# untitled.net
KiCad netlist of a schematic drawn in EAGLE
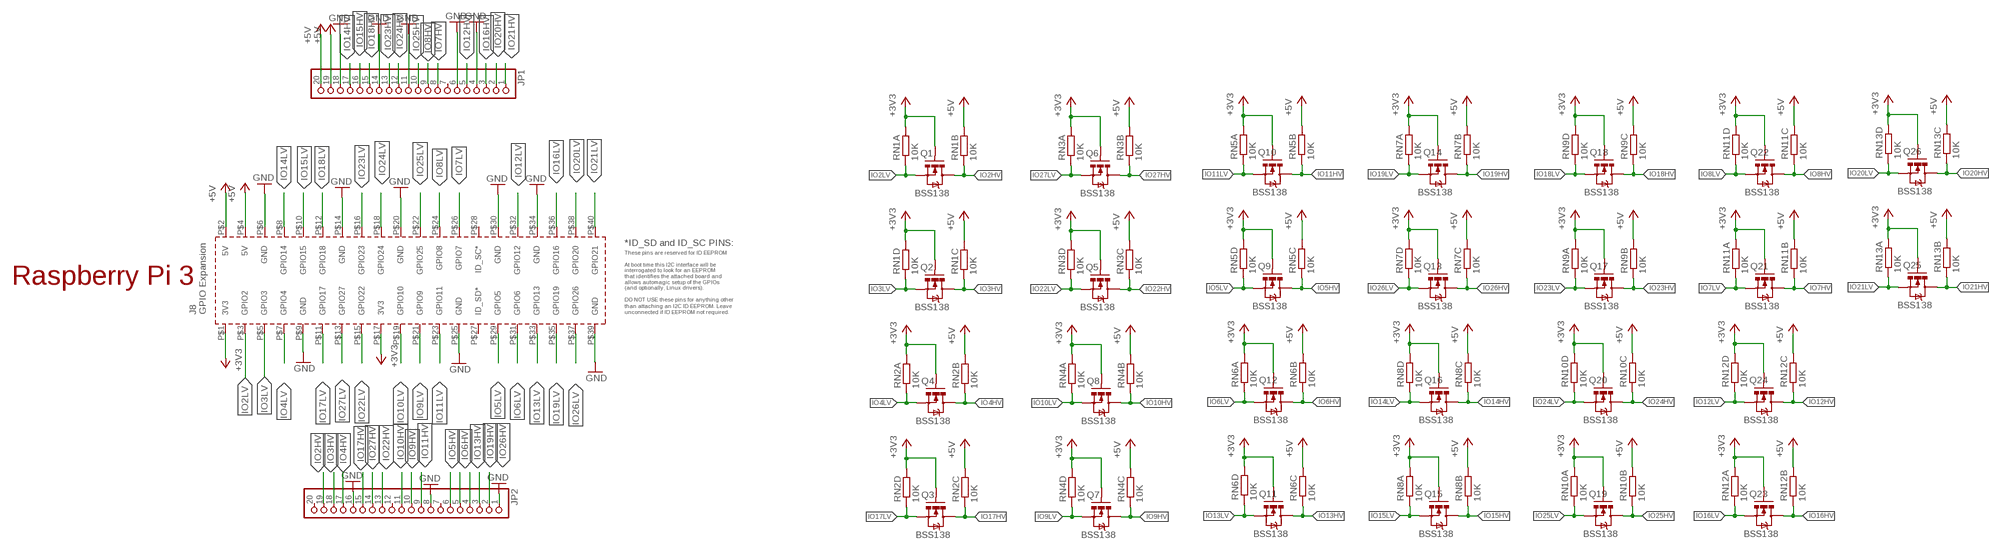
[diagram p0: schematic, sheet 1]

(export (version "E")
  (design (tool "Eeschema 10.0.6"))
  (components
    (comp (ref "JP1")
      (value "PINHD-1X20-BIG")
      (footprint "eagle-import:1X20-BIG")
      (libsource (lib "eagle-import") (part "PINHD-1X20-BIG"))
    )
    (comp (ref "JP2")
      (value "PINHD-1X20-BIG")
      (footprint "eagle-import:1X20-BIG")
      (libsource (lib "eagle-import") (part "PINHD-1X20-BIG"))
    )
    (comp (ref "Q1")
      (value "BSS138")
      (footprint "eagle-import:SOT23-3")
      (libsource (lib "eagle-import") (part "MOSFET-NCHANNELSMD"))
    )
    (comp (ref "Q2")
      (value "BSS138")
      (footprint "eagle-import:SOT23-3")
      (libsource (lib "eagle-import") (part "MOSFET-NCHANNELSMD"))
    )
    (comp (ref "Q3")
      (value "BSS138")
      (footprint "eagle-import:SOT23-3")
      (libsource (lib "eagle-import") (part "MOSFET-NCHANNELSMD"))
    )
    (comp (ref "Q4")
      (value "BSS138")
      (footprint "eagle-import:SOT23-3")
      (libsource (lib "eagle-import") (part "MOSFET-NCHANNELSMD"))
    )
    (comp (ref "Q5")
      (value "BSS138")
      (footprint "eagle-import:SOT23-3")
      (libsource (lib "eagle-import") (part "MOSFET-NCHANNELSMD"))
    )
    (comp (ref "Q6")
      (value "BSS138")
      (footprint "eagle-import:SOT23-3")
      (libsource (lib "eagle-import") (part "MOSFET-NCHANNELSMD"))
    )
    (comp (ref "Q7")
      (value "BSS138")
      (footprint "eagle-import:SOT23-3")
      (libsource (lib "eagle-import") (part "MOSFET-NCHANNELSMD"))
    )
    (comp (ref "Q8")
      (value "BSS138")
      (footprint "eagle-import:SOT23-3")
      (libsource (lib "eagle-import") (part "MOSFET-NCHANNELSMD"))
    )
    (comp (ref "Q9")
      (value "BSS138")
      (footprint "eagle-import:SOT23-3")
      (libsource (lib "eagle-import") (part "MOSFET-NCHANNELSMD"))
    )
    (comp (ref "Q10")
      (value "BSS138")
      (footprint "eagle-import:SOT23-3")
      (libsource (lib "eagle-import") (part "MOSFET-NCHANNELSMD"))
    )
    (comp (ref "Q11")
      (value "BSS138")
      (footprint "eagle-import:SOT23-3")
      (libsource (lib "eagle-import") (part "MOSFET-NCHANNELSMD"))
    )
    (comp (ref "Q12")
      (value "BSS138")
      (footprint "eagle-import:SOT23-3")
      (libsource (lib "eagle-import") (part "MOSFET-NCHANNELSMD"))
    )
    (comp (ref "Q13")
      (value "BSS138")
      (footprint "eagle-import:SOT23-3")
      (libsource (lib "eagle-import") (part "MOSFET-NCHANNELSMD"))
    )
    (comp (ref "Q14")
      (value "BSS138")
      (footprint "eagle-import:SOT23-3")
      (libsource (lib "eagle-import") (part "MOSFET-NCHANNELSMD"))
    )
    (comp (ref "Q15")
      (value "BSS138")
      (footprint "eagle-import:SOT23-3")
      (libsource (lib "eagle-import") (part "MOSFET-NCHANNELSMD"))
    )
    (comp (ref "Q16")
      (value "BSS138")
      (footprint "eagle-import:SOT23-3")
      (libsource (lib "eagle-import") (part "MOSFET-NCHANNELSMD"))
    )
    (comp (ref "Q17")
      (value "BSS138")
      (footprint "eagle-import:SOT23-3")
      (libsource (lib "eagle-import") (part "MOSFET-NCHANNELSMD"))
    )
    (comp (ref "Q18")
      (value "BSS138")
      (footprint "eagle-import:SOT23-3")
      (libsource (lib "eagle-import") (part "MOSFET-NCHANNELSMD"))
    )
    (comp (ref "Q19")
      (value "BSS138")
      (footprint "eagle-import:SOT23-3")
      (libsource (lib "eagle-import") (part "MOSFET-NCHANNELSMD"))
    )
    (comp (ref "Q20")
      (value "BSS138")
      (footprint "eagle-import:SOT23-3")
      (libsource (lib "eagle-import") (part "MOSFET-NCHANNELSMD"))
    )
    (comp (ref "Q21")
      (value "BSS138")
      (footprint "eagle-import:SOT23-3")
      (libsource (lib "eagle-import") (part "MOSFET-NCHANNELSMD"))
    )
    (comp (ref "Q22")
      (value "BSS138")
      (footprint "eagle-import:SOT23-3")
      (libsource (lib "eagle-import") (part "MOSFET-NCHANNELSMD"))
    )
    (comp (ref "Q23")
      (value "BSS138")
      (footprint "eagle-import:SOT23-3")
      (libsource (lib "eagle-import") (part "MOSFET-NCHANNELSMD"))
    )
    (comp (ref "Q24")
      (value "BSS138")
      (footprint "eagle-import:SOT23-3")
      (libsource (lib "eagle-import") (part "MOSFET-NCHANNELSMD"))
    )
    (comp (ref "Q25")
      (value "BSS138")
      (footprint "eagle-import:SOT23-3")
      (libsource (lib "eagle-import") (part "MOSFET-NCHANNELSMD"))
    )
    (comp (ref "Q26")
      (value "BSS138")
      (footprint "eagle-import:SOT23-3")
      (libsource (lib "eagle-import") (part "MOSFET-NCHANNELSMD"))
    )
    (comp (ref "RN1")
      (value "10K")
      (footprint "eagle-import:RN8P-4R-CRA06S")
      (libsource (lib "eagle-import") (part "RESISTOR_ARRAY_4"))
    )
    (comp (ref "RN2")
      (value "10K")
      (footprint "eagle-import:RN8P-4R-CRA06S")
      (libsource (lib "eagle-import") (part "RESISTOR_ARRAY_4"))
    )
    (comp (ref "RN3")
      (value "10K")
      (footprint "eagle-import:RN8P-4R-CRA06S")
      (libsource (lib "eagle-import") (part "RESISTOR_ARRAY_4"))
    )
    (comp (ref "RN4")
      (value "10K")
      (footprint "eagle-import:RN8P-4R-CRA06S")
      (libsource (lib "eagle-import") (part "RESISTOR_ARRAY_4"))
    )
    (comp (ref "RN5")
      (value "10K")
      (footprint "eagle-import:RN8P-4R-CRA06S")
      (libsource (lib "eagle-import") (part "RESISTOR_ARRAY_4"))
    )
    (comp (ref "RN6")
      (value "10K")
      (footprint "eagle-import:RN8P-4R-CRA06S")
      (libsource (lib "eagle-import") (part "RESISTOR_ARRAY_4"))
    )
    (comp (ref "RN7")
      (value "10K")
      (footprint "eagle-import:RN8P-4R-CRA06S")
      (libsource (lib "eagle-import") (part "RESISTOR_ARRAY_4"))
    )
    (comp (ref "RN8")
      (value "10K")
      (footprint "eagle-import:RN8P-4R-CRA06S")
      (libsource (lib "eagle-import") (part "RESISTOR_ARRAY_4"))
    )
    (comp (ref "RN9")
      (value "10K")
      (footprint "eagle-import:RN8P-4R-CRA06S")
      (libsource (lib "eagle-import") (part "RESISTOR_ARRAY_4"))
    )
    (comp (ref "RN10")
      (value "10K")
      (footprint "eagle-import:RN8P-4R-CRA06S")
      (libsource (lib "eagle-import") (part "RESISTOR_ARRAY_4"))
    )
    (comp (ref "RN11")
      (value "10K")
      (footprint "eagle-import:RN8P-4R-CRA06S")
      (libsource (lib "eagle-import") (part "RESISTOR_ARRAY_4"))
    )
    (comp (ref "RN12")
      (value "10K")
      (footprint "eagle-import:RN8P-4R-CRA06S")
      (libsource (lib "eagle-import") (part "RESISTOR_ARRAY_4"))
    )
    (comp (ref "RN13")
      (value "10K")
      (footprint "eagle-import:RN8P-4R-CRA06S")
      (libsource (lib "eagle-import") (part "RESISTOR_ARRAY_4"))
    )
    (comp (ref "U$2")
      (value "RPI3HEADERS")
      (footprint "eagle-import:RPI3HEADERS")
      (libsource (lib "eagle-import") (part "RPI3HEADERS"))
    )
  )
  (nets
    (net (code "1") (name "+3V3") (class "Default")
      (node (ref "Q1") (pin "1") (pinfunction "G_1") (pintype "passive"))
      (node (ref "Q10") (pin "1") (pinfunction "G_1") (pintype "passive"))
      (node (ref "Q11") (pin "1") (pinfunction "G_1") (pintype "passive"))
      (node (ref "Q12") (pin "1") (pinfunction "G_1") (pintype "passive"))
      (node (ref "Q13") (pin "1") (pinfunction "G_1") (pintype "passive"))
      (node (ref "Q14") (pin "1") (pinfunction "G_1") (pintype "passive"))
      (node (ref "Q15") (pin "1") (pinfunction "G_1") (pintype "passive"))
      (node (ref "Q16") (pin "1") (pinfunction "G_1") (pintype "passive"))
      (node (ref "Q17") (pin "1") (pinfunction "G_1") (pintype "passive"))
      (node (ref "Q18") (pin "1") (pinfunction "G_1") (pintype "passive"))
      (node (ref "Q19") (pin "1") (pinfunction "G_1") (pintype "passive"))
      (node (ref "Q2") (pin "1") (pinfunction "G_1") (pintype "passive"))
      (node (ref "Q20") (pin "1") (pinfunction "G_1") (pintype "passive"))
      (node (ref "Q21") (pin "1") (pinfunction "G_1") (pintype "passive"))
      (node (ref "Q22") (pin "1") (pinfunction "G_1") (pintype "passive"))
      (node (ref "Q23") (pin "1") (pinfunction "G_1") (pintype "passive"))
      (node (ref "Q24") (pin "1") (pinfunction "G_1") (pintype "passive"))
      (node (ref "Q25") (pin "1") (pinfunction "G_1") (pintype "passive"))
      (node (ref "Q26") (pin "1") (pinfunction "G_1") (pintype "passive"))
      (node (ref "Q3") (pin "1") (pinfunction "G_1") (pintype "passive"))
      (node (ref "Q4") (pin "1") (pinfunction "G_1") (pintype "passive"))
      (node (ref "Q5") (pin "1") (pinfunction "G_1") (pintype "passive"))
      (node (ref "Q6") (pin "1") (pinfunction "G_1") (pintype "passive"))
      (node (ref "Q7") (pin "1") (pinfunction "G_1") (pintype "passive"))
      (node (ref "Q8") (pin "1") (pinfunction "G_1") (pintype "passive"))
      (node (ref "Q9") (pin "1") (pinfunction "G_1") (pintype "passive"))
      (node (ref "RN1") (pin "5") (pinfunction "2_5") (pintype "passive"))
      (node (ref "RN1") (pin "8") (pinfunction "2_8") (pintype "passive"))
      (node (ref "RN10") (pin "5") (pinfunction "2_5") (pintype "passive"))
      (node (ref "RN10") (pin "8") (pinfunction "2_8") (pintype "passive"))
      (node (ref "RN11") (pin "5") (pinfunction "2_5") (pintype "passive"))
      (node (ref "RN11") (pin "8") (pinfunction "2_8") (pintype "passive"))
      (node (ref "RN12") (pin "5") (pinfunction "2_5") (pintype "passive"))
      (node (ref "RN12") (pin "8") (pinfunction "2_8") (pintype "passive"))
      (node (ref "RN13") (pin "5") (pinfunction "2_5") (pintype "passive"))
      (node (ref "RN13") (pin "8") (pinfunction "2_8") (pintype "passive"))
      (node (ref "RN2") (pin "5") (pinfunction "2_5") (pintype "passive"))
      (node (ref "RN2") (pin "8") (pinfunction "2_8") (pintype "passive"))
      (node (ref "RN3") (pin "5") (pinfunction "2_5") (pintype "passive"))
      (node (ref "RN3") (pin "8") (pinfunction "2_8") (pintype "passive"))
      (node (ref "RN4") (pin "5") (pinfunction "2_5") (pintype "passive"))
      (node (ref "RN4") (pin "8") (pinfunction "2_8") (pintype "passive"))
      (node (ref "RN5") (pin "5") (pinfunction "2_5") (pintype "passive"))
      (node (ref "RN5") (pin "8") (pinfunction "2_8") (pintype "passive"))
      (node (ref "RN6") (pin "5") (pinfunction "2_5") (pintype "passive"))
      (node (ref "RN6") (pin "8") (pinfunction "2_8") (pintype "passive"))
      (node (ref "RN7") (pin "5") (pinfunction "2_5") (pintype "passive"))
      (node (ref "RN7") (pin "8") (pinfunction "2_8") (pintype "passive"))
      (node (ref "RN8") (pin "5") (pinfunction "2_5") (pintype "passive"))
      (node (ref "RN8") (pin "8") (pinfunction "2_8") (pintype "passive"))
      (node (ref "RN9") (pin "5") (pinfunction "2_5") (pintype "passive"))
      (node (ref "RN9") (pin "8") (pinfunction "2_8") (pintype "passive"))
      (node (ref "U$2") (pin "P$1") (pinfunction "3V3_P$1") (pintype "bidirectional"))
      (node (ref "U$2") (pin "P$17") (pinfunction "3V3_P$17") (pintype "bidirectional"))
    )
    (net (code "2") (name "+5V") (class "Default")
      (node (ref "JP1") (pin "19") (pinfunction "19_19") (pintype "passive"))
      (node (ref "JP1") (pin "20") (pinfunction "20_20") (pintype "passive"))
      (node (ref "RN1") (pin "6") (pinfunction "2_6") (pintype "passive"))
      (node (ref "RN1") (pin "7") (pinfunction "2_7") (pintype "passive"))
      (node (ref "RN10") (pin "6") (pinfunction "2_6") (pintype "passive"))
      (node (ref "RN10") (pin "7") (pinfunction "2_7") (pintype "passive"))
      (node (ref "RN11") (pin "6") (pinfunction "2_6") (pintype "passive"))
      (node (ref "RN11") (pin "7") (pinfunction "2_7") (pintype "passive"))
      (node (ref "RN12") (pin "6") (pinfunction "2_6") (pintype "passive"))
      (node (ref "RN12") (pin "7") (pinfunction "2_7") (pintype "passive"))
      (node (ref "RN13") (pin "6") (pinfunction "2_6") (pintype "passive"))
      (node (ref "RN13") (pin "7") (pinfunction "2_7") (pintype "passive"))
      (node (ref "RN2") (pin "6") (pinfunction "2_6") (pintype "passive"))
      (node (ref "RN2") (pin "7") (pinfunction "2_7") (pintype "passive"))
      (node (ref "RN3") (pin "6") (pinfunction "2_6") (pintype "passive"))
      (node (ref "RN3") (pin "7") (pinfunction "2_7") (pintype "passive"))
      (node (ref "RN4") (pin "6") (pinfunction "2_6") (pintype "passive"))
      (node (ref "RN4") (pin "7") (pinfunction "2_7") (pintype "passive"))
      (node (ref "RN5") (pin "6") (pinfunction "2_6") (pintype "passive"))
      (node (ref "RN5") (pin "7") (pinfunction "2_7") (pintype "passive"))
      (node (ref "RN6") (pin "6") (pinfunction "2_6") (pintype "passive"))
      (node (ref "RN6") (pin "7") (pinfunction "2_7") (pintype "passive"))
      (node (ref "RN7") (pin "6") (pinfunction "2_6") (pintype "passive"))
      (node (ref "RN7") (pin "7") (pinfunction "2_7") (pintype "passive"))
      (node (ref "RN8") (pin "6") (pinfunction "2_6") (pintype "passive"))
      (node (ref "RN8") (pin "7") (pinfunction "2_7") (pintype "passive"))
      (node (ref "RN9") (pin "6") (pinfunction "2_6") (pintype "passive"))
      (node (ref "RN9") (pin "7") (pinfunction "2_7") (pintype "passive"))
      (node (ref "U$2") (pin "P$2") (pinfunction "5V_P$2") (pintype "bidirectional"))
      (node (ref "U$2") (pin "P$4") (pinfunction "5V_P$4") (pintype "bidirectional"))
    )
    (net (code "3") (name "GND") (class "Default")
      (node (ref "JP1") (pin "11") (pinfunction "11_11") (pintype "passive"))
      (node (ref "JP1") (pin "14") (pinfunction "14_14") (pintype "passive"))
      (node (ref "JP1") (pin "18") (pinfunction "18_18") (pintype "passive"))
      (node (ref "JP1") (pin "4") (pinfunction "4_4") (pintype "passive"))
      (node (ref "JP1") (pin "6") (pinfunction "6_6") (pintype "passive"))
      (node (ref "JP2") (pin "1") (pinfunction "1_1") (pintype "passive"))
      (node (ref "JP2") (pin "16") (pinfunction "16_16") (pintype "passive"))
      (node (ref "JP2") (pin "8") (pinfunction "8_8") (pintype "passive"))
      (node (ref "U$2") (pin "P$14") (pinfunction "GND_P$14") (pintype "bidirectional"))
      (node (ref "U$2") (pin "P$20") (pinfunction "GND_P$20") (pintype "bidirectional"))
      (node (ref "U$2") (pin "P$25") (pinfunction "GND_P$25") (pintype "bidirectional"))
      (node (ref "U$2") (pin "P$30") (pinfunction "GND_P$30") (pintype "bidirectional"))
      (node (ref "U$2") (pin "P$34") (pinfunction "GND_P$34") (pintype "bidirectional"))
      (node (ref "U$2") (pin "P$39") (pinfunction "GND_P$39") (pintype "bidirectional"))
      (node (ref "U$2") (pin "P$6") (pinfunction "GND_P$6") (pintype "bidirectional"))
      (node (ref "U$2") (pin "P$9") (pinfunction "GND_P$9") (pintype "bidirectional"))
    )
    (net (code "4") (name "IO2HV") (class "Default")
      (node (ref "JP2") (pin "19") (pinfunction "19_19") (pintype "passive"))
      (node (ref "Q1") (pin "3") (pinfunction "D_3") (pintype "passive"))
      (node (ref "RN1") (pin "2") (pinfunction "1_2") (pintype "passive"))
    )
    (net (code "5") (name "IO2LV") (class "Default")
      (node (ref "Q1") (pin "2") (pinfunction "S_2") (pintype "passive"))
      (node (ref "RN1") (pin "1") (pinfunction "1_1") (pintype "passive"))
      (node (ref "U$2") (pin "P$3") (pinfunction "GPIO2_P$3") (pintype "bidirectional"))
    )
    (net (code "6") (name "IO3HV") (class "Default")
      (node (ref "JP2") (pin "18") (pinfunction "18_18") (pintype "passive"))
      (node (ref "Q2") (pin "3") (pinfunction "D_3") (pintype "passive"))
      (node (ref "RN1") (pin "3") (pinfunction "1_3") (pintype "passive"))
    )
    (net (code "7") (name "IO3LV") (class "Default")
      (node (ref "Q2") (pin "2") (pinfunction "S_2") (pintype "passive"))
      (node (ref "RN1") (pin "4") (pinfunction "1_4") (pintype "passive"))
      (node (ref "U$2") (pin "P$5") (pinfunction "GPIO3_P$5") (pintype "bidirectional"))
    )
    (net (code "8") (name "IO4HV") (class "Default")
      (node (ref "JP2") (pin "17") (pinfunction "17_17") (pintype "passive"))
      (node (ref "Q4") (pin "3") (pinfunction "D_3") (pintype "passive"))
      (node (ref "RN2") (pin "2") (pinfunction "1_2") (pintype "passive"))
    )
    (net (code "9") (name "IO4LV") (class "Default")
      (node (ref "Q4") (pin "2") (pinfunction "S_2") (pintype "passive"))
      (node (ref "RN2") (pin "1") (pinfunction "1_1") (pintype "passive"))
      (node (ref "U$2") (pin "P$7") (pinfunction "GPIO4_P$7") (pintype "bidirectional"))
    )
    (net (code "10") (name "IO5HV") (class "Default")
      (node (ref "JP2") (pin "6") (pinfunction "6_6") (pintype "passive"))
      (node (ref "Q9") (pin "3") (pinfunction "D_3") (pintype "passive"))
      (node (ref "RN5") (pin "3") (pinfunction "1_3") (pintype "passive"))
    )
    (net (code "11") (name "IO5LV") (class "Default")
      (node (ref "Q9") (pin "2") (pinfunction "S_2") (pintype "passive"))
      (node (ref "RN5") (pin "4") (pinfunction "1_4") (pintype "passive"))
      (node (ref "U$2") (pin "P$29") (pinfunction "GPIO5_P$29") (pintype "bidirectional"))
    )
    (net (code "12") (name "IO6HV") (class "Default")
      (node (ref "JP2") (pin "5") (pinfunction "5_5") (pintype "passive"))
      (node (ref "Q12") (pin "3") (pinfunction "D_3") (pintype "passive"))
      (node (ref "RN6") (pin "2") (pinfunction "1_2") (pintype "passive"))
    )
    (net (code "13") (name "IO6LV") (class "Default")
      (node (ref "Q12") (pin "2") (pinfunction "S_2") (pintype "passive"))
      (node (ref "RN6") (pin "1") (pinfunction "1_1") (pintype "passive"))
      (node (ref "U$2") (pin "P$31") (pinfunction "GPIO6_P$31") (pintype "bidirectional"))
    )
    (net (code "14") (name "IO7HV") (class "Default")
      (node (ref "JP1") (pin "8") (pinfunction "8_8") (pintype "passive"))
      (node (ref "Q21") (pin "3") (pinfunction "D_3") (pintype "passive"))
      (node (ref "RN11") (pin "2") (pinfunction "1_2") (pintype "passive"))
    )
    (net (code "15") (name "IO7LV") (class "Default")
      (node (ref "Q21") (pin "2") (pinfunction "S_2") (pintype "passive"))
      (node (ref "RN11") (pin "1") (pinfunction "1_1") (pintype "passive"))
      (node (ref "U$2") (pin "P$26") (pinfunction "GPIO7_P$26") (pintype "bidirectional"))
    )
    (net (code "16") (name "IO8HV") (class "Default")
      (node (ref "JP1") (pin "9") (pinfunction "9_9") (pintype "passive"))
      (node (ref "Q22") (pin "3") (pinfunction "D_3") (pintype "passive"))
      (node (ref "RN11") (pin "3") (pinfunction "1_3") (pintype "passive"))
    )
    (net (code "17") (name "IO8LV") (class "Default")
      (node (ref "Q22") (pin "2") (pinfunction "S_2") (pintype "passive"))
      (node (ref "RN11") (pin "4") (pinfunction "1_4") (pintype "passive"))
      (node (ref "U$2") (pin "P$24") (pinfunction "GPIO8_P$24") (pintype "bidirectional"))
    )
    (net (code "18") (name "IO9HV") (class "Default")
      (node (ref "JP2") (pin "10") (pinfunction "10_10") (pintype "passive"))
      (node (ref "Q7") (pin "3") (pinfunction "D_3") (pintype "passive"))
      (node (ref "RN4") (pin "3") (pinfunction "1_3") (pintype "passive"))
    )
    (net (code "19") (name "IO9LV") (class "Default")
      (node (ref "Q7") (pin "2") (pinfunction "S_2") (pintype "passive"))
      (node (ref "RN4") (pin "4") (pinfunction "1_4") (pintype "passive"))
      (node (ref "U$2") (pin "P$21") (pinfunction "GPIO9_P$21") (pintype "bidirectional"))
    )
    (net (code "20") (name "IO10HV") (class "Default")
      (node (ref "JP2") (pin "11") (pinfunction "11_11") (pintype "passive"))
      (node (ref "Q8") (pin "3") (pinfunction "D_3") (pintype "passive"))
      (node (ref "RN4") (pin "2") (pinfunction "1_2") (pintype "passive"))
    )
    (net (code "21") (name "IO10LV") (class "Default")
      (node (ref "Q8") (pin "2") (pinfunction "S_2") (pintype "passive"))
      (node (ref "RN4") (pin "1") (pinfunction "1_1") (pintype "passive"))
      (node (ref "U$2") (pin "P$19") (pinfunction "GPIO10_P$19") (pintype "bidirectional"))
    )
    (net (code "22") (name "IO11HV") (class "Default")
      (node (ref "JP2") (pin "9") (pinfunction "9_9") (pintype "passive"))
      (node (ref "Q10") (pin "3") (pinfunction "D_3") (pintype "passive"))
      (node (ref "RN5") (pin "2") (pinfunction "1_2") (pintype "passive"))
    )
    (net (code "23") (name "IO11LV") (class "Default")
      (node (ref "Q10") (pin "2") (pinfunction "S_2") (pintype "passive"))
      (node (ref "RN5") (pin "1") (pinfunction "1_1") (pintype "passive"))
      (node (ref "U$2") (pin "P$23") (pinfunction "GPIO11_P$23") (pintype "bidirectional"))
    )
    (net (code "24") (name "IO12HV") (class "Default")
      (node (ref "JP1") (pin "5") (pinfunction "5_5") (pintype "passive"))
      (node (ref "Q24") (pin "3") (pinfunction "D_3") (pintype "passive"))
      (node (ref "RN12") (pin "3") (pinfunction "1_3") (pintype "passive"))
    )
    (net (code "25") (name "IO12LV") (class "Default")
      (node (ref "Q24") (pin "2") (pinfunction "S_2") (pintype "passive"))
      (node (ref "RN12") (pin "4") (pinfunction "1_4") (pintype "passive"))
      (node (ref "U$2") (pin "P$32") (pinfunction "GPIO12_P$32") (pintype "bidirectional"))
    )
    (net (code "26") (name "IO13HV") (class "Default")
      (node (ref "JP2") (pin "4") (pinfunction "4_4") (pintype "passive"))
      (node (ref "Q11") (pin "3") (pinfunction "D_3") (pintype "passive"))
      (node (ref "RN6") (pin "3") (pinfunction "1_3") (pintype "passive"))
    )
    (net (code "27") (name "IO13LV") (class "Default")
      (node (ref "Q11") (pin "2") (pinfunction "S_2") (pintype "passive"))
      (node (ref "RN6") (pin "4") (pinfunction "1_4") (pintype "passive"))
      (node (ref "U$2") (pin "P$33") (pinfunction "GPIO13_P$33") (pintype "bidirectional"))
    )
    (net (code "28") (name "IO14HV") (class "Default")
      (node (ref "JP1") (pin "17") (pinfunction "17_17") (pintype "passive"))
      (node (ref "Q16") (pin "3") (pinfunction "D_3") (pintype "passive"))
      (node (ref "RN8") (pin "3") (pinfunction "1_3") (pintype "passive"))
    )
    (net (code "29") (name "IO14LV") (class "Default")
      (node (ref "Q16") (pin "2") (pinfunction "S_2") (pintype "passive"))
      (node (ref "RN8") (pin "4") (pinfunction "1_4") (pintype "passive"))
      (node (ref "U$2") (pin "P$8") (pinfunction "GPIO14_P$8") (pintype "bidirectional"))
    )
    (net (code "30") (name "IO15HV") (class "Default")
      (node (ref "JP1") (pin "16") (pinfunction "16_16") (pintype "passive"))
      (node (ref "Q15") (pin "3") (pinfunction "D_3") (pintype "passive"))
      (node (ref "RN8") (pin "2") (pinfunction "1_2") (pintype "passive"))
    )
    (net (code "31") (name "IO15LV") (class "Default")
      (node (ref "Q15") (pin "2") (pinfunction "S_2") (pintype "passive"))
      (node (ref "RN8") (pin "1") (pinfunction "1_1") (pintype "passive"))
      (node (ref "U$2") (pin "P$10") (pinfunction "GPIO15_P$10") (pintype "bidirectional"))
    )
    (net (code "32") (name "IO16HV") (class "Default")
      (node (ref "JP1") (pin "3") (pinfunction "3_3") (pintype "passive"))
      (node (ref "Q23") (pin "3") (pinfunction "D_3") (pintype "passive"))
      (node (ref "RN12") (pin "2") (pinfunction "1_2") (pintype "passive"))
    )
    (net (code "33") (name "IO16LV") (class "Default")
      (node (ref "Q23") (pin "2") (pinfunction "S_2") (pintype "passive"))
      (node (ref "RN12") (pin "1") (pinfunction "1_1") (pintype "passive"))
      (node (ref "U$2") (pin "P$36") (pinfunction "GPIO16_P$36") (pintype "bidirectional"))
    )
    (net (code "34") (name "IO17HV") (class "Default")
      (node (ref "JP2") (pin "15") (pinfunction "15_15") (pintype "passive"))
      (node (ref "Q3") (pin "3") (pinfunction "D_3") (pintype "passive"))
      (node (ref "RN2") (pin "3") (pinfunction "1_3") (pintype "passive"))
    )
    (net (code "35") (name "IO17LV") (class "Default")
      (node (ref "Q3") (pin "2") (pinfunction "S_2") (pintype "passive"))
      (node (ref "RN2") (pin "4") (pinfunction "1_4") (pintype "passive"))
      (node (ref "U$2") (pin "P$11") (pinfunction "GPIO17_P$11") (pintype "bidirectional"))
    )
    (net (code "36") (name "IO18HV") (class "Default")
      (node (ref "JP1") (pin "15") (pinfunction "15_15") (pintype "passive"))
      (node (ref "Q18") (pin "3") (pinfunction "D_3") (pintype "passive"))
      (node (ref "RN9") (pin "3") (pinfunction "1_3") (pintype "passive"))
    )
    (net (code "37") (name "IO18LV") (class "Default")
      (node (ref "Q18") (pin "2") (pinfunction "S_2") (pintype "passive"))
      (node (ref "RN9") (pin "4") (pinfunction "1_4") (pintype "passive"))
      (node (ref "U$2") (pin "P$12") (pinfunction "GPIO18_P$12") (pintype "bidirectional"))
    )
    (net (code "38") (name "IO19HV") (class "Default")
      (node (ref "JP2") (pin "3") (pinfunction "3_3") (pintype "passive"))
      (node (ref "Q14") (pin "3") (pinfunction "D_3") (pintype "passive"))
      (node (ref "RN7") (pin "2") (pinfunction "1_2") (pintype "passive"))
    )
    (net (code "39") (name "IO19LV") (class "Default")
      (node (ref "Q14") (pin "2") (pinfunction "S_2") (pintype "passive"))
      (node (ref "RN7") (pin "1") (pinfunction "1_1") (pintype "passive"))
      (node (ref "U$2") (pin "P$35") (pinfunction "GPIO19_P$35") (pintype "bidirectional"))
    )
    (net (code "40") (name "IO20HV") (class "Default")
      (node (ref "JP1") (pin "2") (pinfunction "2_2") (pintype "passive"))
      (node (ref "Q26") (pin "3") (pinfunction "D_3") (pintype "passive"))
      (node (ref "RN13") (pin "3") (pinfunction "1_3") (pintype "passive"))
    )
    (net (code "41") (name "IO20LV") (class "Default")
      (node (ref "Q26") (pin "2") (pinfunction "S_2") (pintype "passive"))
      (node (ref "RN13") (pin "4") (pinfunction "1_4") (pintype "passive"))
      (node (ref "U$2") (pin "P$38") (pinfunction "GPIO20_P$38") (pintype "bidirectional"))
    )
    (net (code "42") (name "IO21HV") (class "Default")
      (node (ref "JP1") (pin "1") (pinfunction "1_1") (pintype "passive"))
      (node (ref "Q25") (pin "3") (pinfunction "D_3") (pintype "passive"))
      (node (ref "RN13") (pin "2") (pinfunction "1_2") (pintype "passive"))
    )
    (net (code "43") (name "IO21LV") (class "Default")
      (node (ref "Q25") (pin "2") (pinfunction "S_2") (pintype "passive"))
      (node (ref "RN13") (pin "1") (pinfunction "1_1") (pintype "passive"))
      (node (ref "U$2") (pin "P$40") (pinfunction "GPIO21_P$40") (pintype "bidirectional"))
    )
    (net (code "44") (name "IO22HV") (class "Default")
      (node (ref "JP2") (pin "13") (pinfunction "13_13") (pintype "passive"))
      (node (ref "Q5") (pin "3") (pinfunction "D_3") (pintype "passive"))
      (node (ref "RN3") (pin "3") (pinfunction "1_3") (pintype "passive"))
    )
    (net (code "45") (name "IO22LV") (class "Default")
      (node (ref "Q5") (pin "2") (pinfunction "S_2") (pintype "passive"))
      (node (ref "RN3") (pin "4") (pinfunction "1_4") (pintype "passive"))
      (node (ref "U$2") (pin "P$15") (pinfunction "GPIO22_P$15") (pintype "bidirectional"))
    )
    (net (code "46") (name "IO23HV") (class "Default")
      (node (ref "JP1") (pin "13") (pinfunction "13_13") (pintype "passive"))
      (node (ref "Q17") (pin "3") (pinfunction "D_3") (pintype "passive"))
      (node (ref "RN9") (pin "2") (pinfunction "1_2") (pintype "passive"))
    )
    (net (code "47") (name "IO23LV") (class "Default")
      (node (ref "Q17") (pin "2") (pinfunction "S_2") (pintype "passive"))
      (node (ref "RN9") (pin "1") (pinfunction "1_1") (pintype "passive"))
      (node (ref "U$2") (pin "P$16") (pinfunction "GPIO23_P$16") (pintype "bidirectional"))
    )
    (net (code "48") (name "IO24HV") (class "Default")
      (node (ref "JP1") (pin "12") (pinfunction "12_12") (pintype "passive"))
      (node (ref "Q20") (pin "3") (pinfunction "D_3") (pintype "passive"))
      (node (ref "RN10") (pin "3") (pinfunction "1_3") (pintype "passive"))
    )
    (net (code "49") (name "IO24LV") (class "Default")
      (node (ref "Q20") (pin "2") (pinfunction "S_2") (pintype "passive"))
      (node (ref "RN10") (pin "4") (pinfunction "1_4") (pintype "passive"))
      (node (ref "U$2") (pin "P$18") (pinfunction "GPIO24_P$18") (pintype "bidirectional"))
    )
    (net (code "50") (name "IO25HV") (class "Default")
      (node (ref "JP1") (pin "10") (pinfunction "10_10") (pintype "passive"))
      (node (ref "Q19") (pin "3") (pinfunction "D_3") (pintype "passive"))
      (node (ref "RN10") (pin "2") (pinfunction "1_2") (pintype "passive"))
    )
    (net (code "51") (name "IO25LV") (class "Default")
      (node (ref "Q19") (pin "2") (pinfunction "S_2") (pintype "passive"))
      (node (ref "RN10") (pin "1") (pinfunction "1_1") (pintype "passive"))
      (node (ref "U$2") (pin "P$22") (pinfunction "GPIO25_P$22") (pintype "bidirectional"))
    )
    (net (code "52") (name "IO26HV") (class "Default")
      (node (ref "JP2") (pin "2") (pinfunction "2_2") (pintype "passive"))
      (node (ref "Q13") (pin "3") (pinfunction "D_3") (pintype "passive"))
      (node (ref "RN7") (pin "3") (pinfunction "1_3") (pintype "passive"))
    )
    (net (code "53") (name "IO26LV") (class "Default")
      (node (ref "Q13") (pin "2") (pinfunction "S_2") (pintype "passive"))
      (node (ref "RN7") (pin "4") (pinfunction "1_4") (pintype "passive"))
      (node (ref "U$2") (pin "P$37") (pinfunction "GPIO26_P$37") (pintype "bidirectional"))
    )
    (net (code "54") (name "IO27HV") (class "Default")
      (node (ref "JP2") (pin "14") (pinfunction "14_14") (pintype "passive"))
      (node (ref "Q6") (pin "3") (pinfunction "D_3") (pintype "passive"))
      (node (ref "RN3") (pin "2") (pinfunction "1_2") (pintype "passive"))
    )
    (net (code "55") (name "IO27LV") (class "Default")
      (node (ref "Q6") (pin "2") (pinfunction "S_2") (pintype "passive"))
      (node (ref "RN3") (pin "1") (pinfunction "1_1") (pintype "passive"))
      (node (ref "U$2") (pin "P$13") (pinfunction "GPIO27_P$13") (pintype "bidirectional"))
    )
    (net (code "56") (name "unconnected-(JP1-Pad7)") (class "Default")
      (node (ref "JP1") (pin "7") (pinfunction "7_7") (pintype "passive"))
    )
    (net (code "57") (name "unconnected-(JP2-Pad7)") (class "Default")
      (node (ref "JP2") (pin "7") (pinfunction "7_7") (pintype "passive"))
    )
    (net (code "58") (name "unconnected-(JP2-Pad12)") (class "Default")
      (node (ref "JP2") (pin "12") (pinfunction "12_12") (pintype "passive"))
    )
    (net (code "59") (name "unconnected-(JP2-Pad20)") (class "Default")
      (node (ref "JP2") (pin "20") (pinfunction "20_20") (pintype "passive"))
    )
    (net (code "60") (name "unconnected-(U$2-ID_SC*-PadP$28)") (class "Default")
      (node (ref "U$2") (pin "P$28") (pinfunction "ID_SC*_P$28") (pintype "bidirectional"))
    )
    (net (code "61") (name "unconnected-(U$2-ID_SD*-PadP$27)") (class "Default")
      (node (ref "U$2") (pin "P$27") (pinfunction "ID_SD*_P$27") (pintype "bidirectional"))
    )
  )
)
